# rfid1.net
KiCad netlist of a schematic drawn in EAGLE
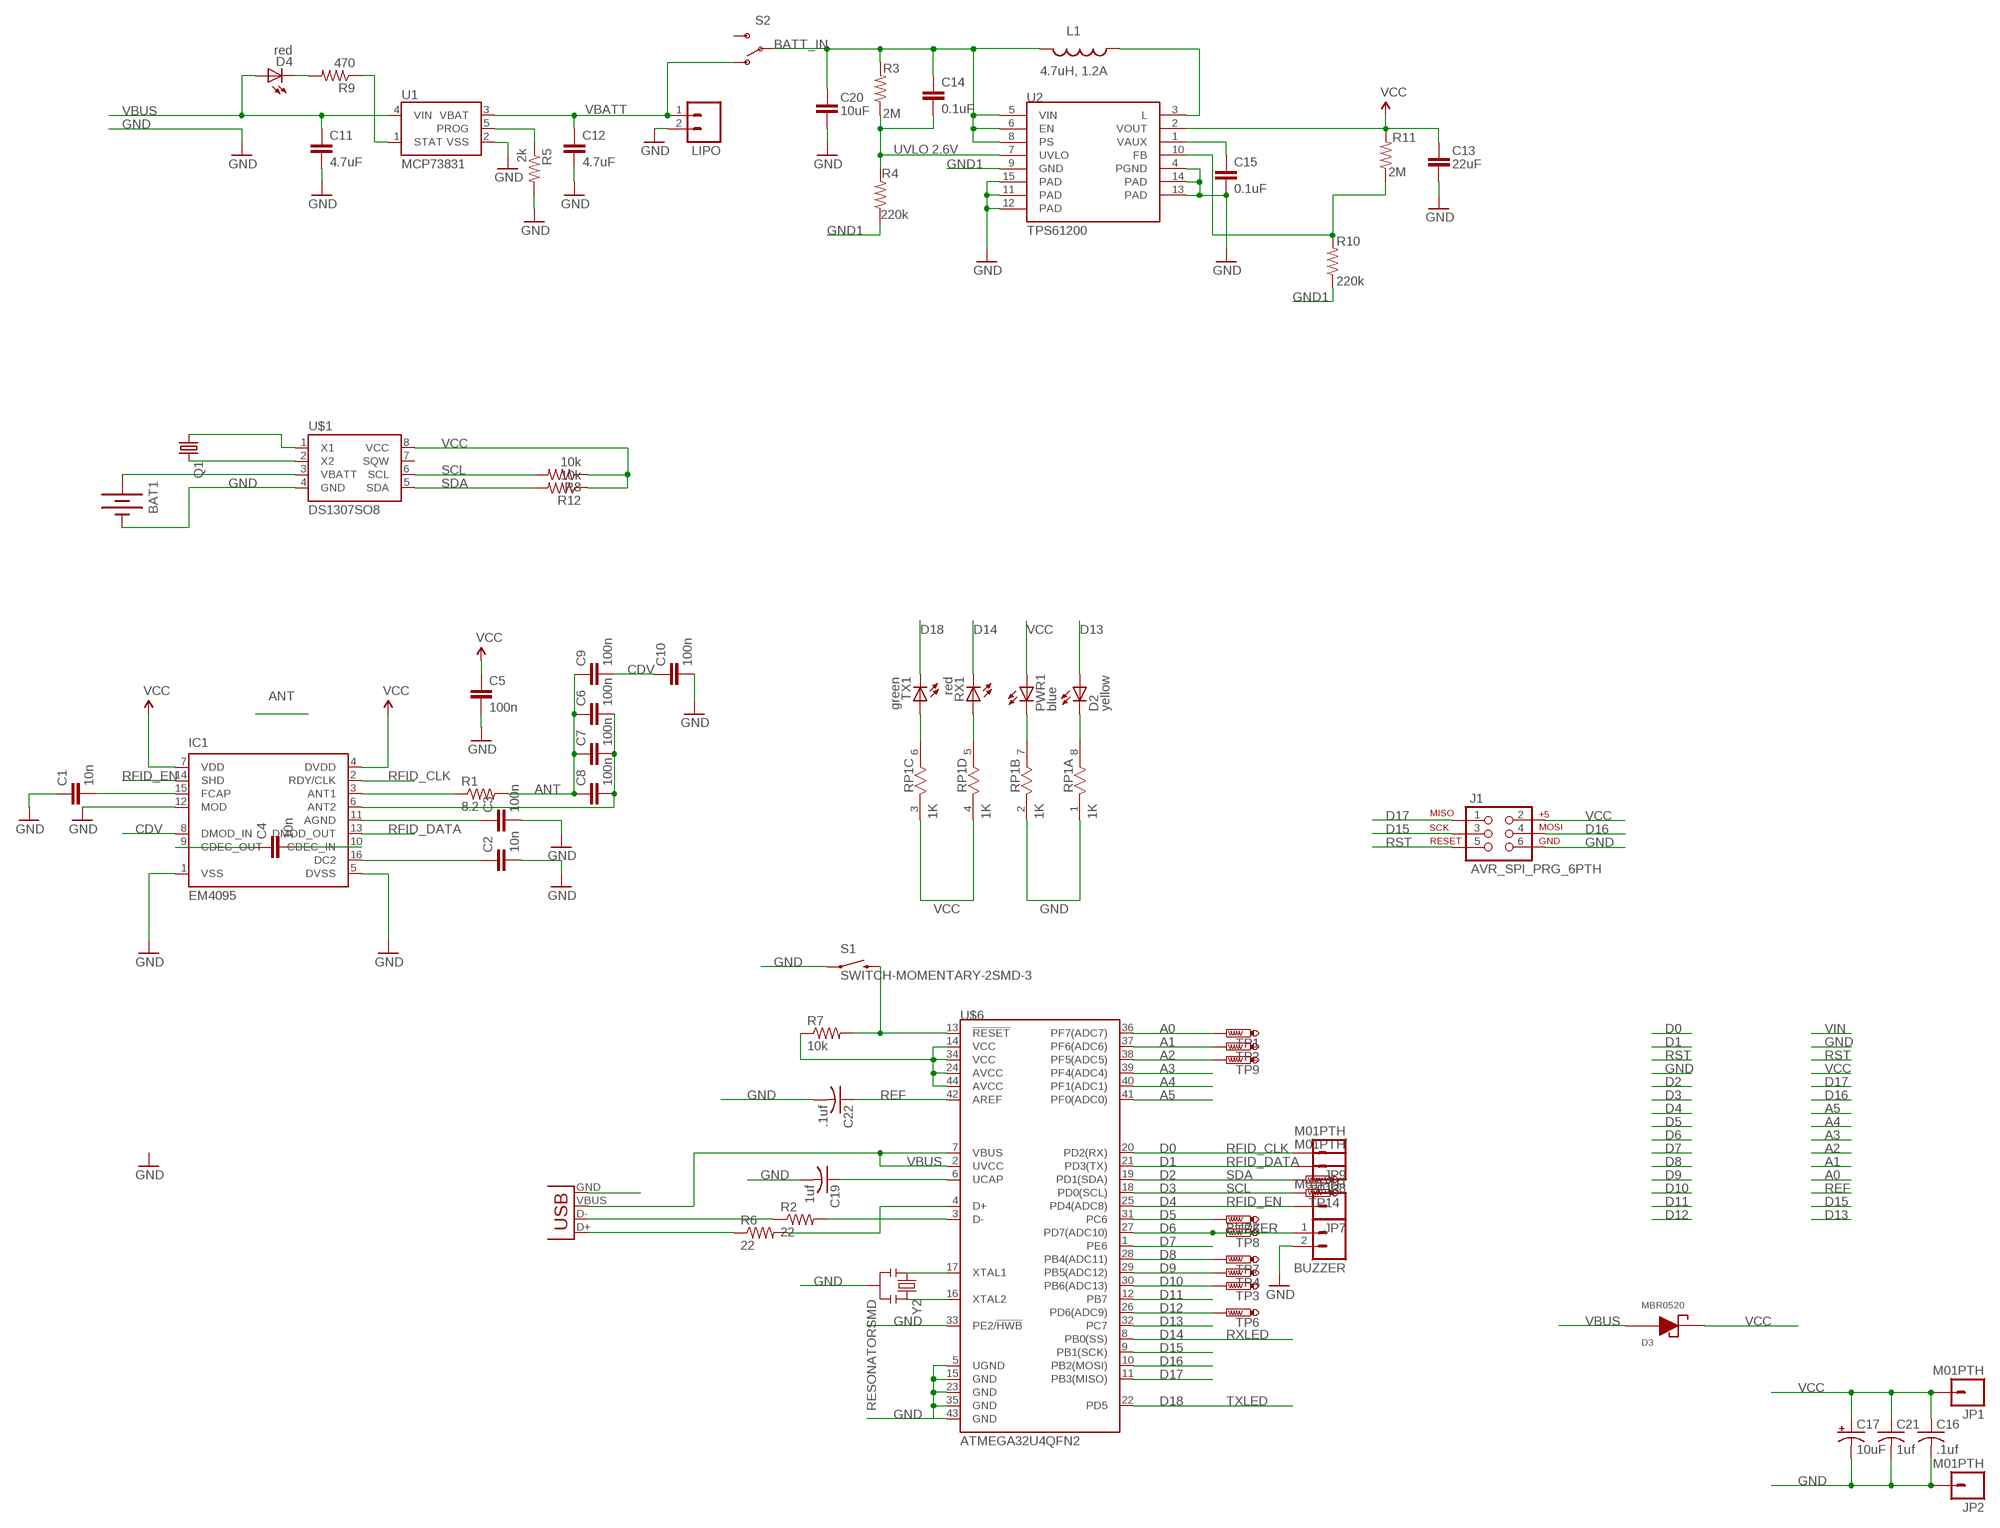
[diagram p0: schematic, sheet 1]

(export (version "E")
  (design (tool "Eeschema 10.0.6"))
  (components
    (comp (ref "BAT1")
      (value "BATTERY12MM")
      (footprint "eagle-import:BATTCON_12MM")
      (libsource (lib "eagle-import") (part "BATTERY12MM"))
    )
    (comp (ref "BUZZER")
      (value "M02PTH")
      (footprint "eagle-import:1X02")
      (libsource (lib "eagle-import") (part "M02PTH"))
    )
    (comp (ref "C1")
      (value "10n")
      (footprint "eagle-import:0805")
      (libsource (lib "eagle-import") (part "SparkFun-Passives_CAP0805"))
    )
    (comp (ref "C2")
      (value "10n")
      (footprint "eagle-import:0805")
      (libsource (lib "eagle-import") (part "SparkFun-Passives_CAP0805"))
    )
    (comp (ref "C3")
      (value "100n")
      (footprint "eagle-import:0805")
      (libsource (lib "eagle-import") (part "SparkFun-Passives_CAP0805"))
    )
    (comp (ref "C4")
      (value "10n")
      (footprint "eagle-import:0805")
      (libsource (lib "eagle-import") (part "SparkFun-Passives_CAP0805"))
    )
    (comp (ref "C5")
      (value "100n")
      (footprint "eagle-import:0805")
      (libsource (lib "eagle-import") (part "SparkFun-Passives_CAP0805"))
    )
    (comp (ref "C6")
      (value "100n")
      (footprint "eagle-import:0805")
      (libsource (lib "eagle-import") (part "SparkFun-Passives_CAP0805"))
    )
    (comp (ref "C7")
      (value "100n")
      (footprint "eagle-import:0805")
      (libsource (lib "eagle-import") (part "SparkFun-Passives_CAP0805"))
    )
    (comp (ref "C8")
      (value "100n")
      (footprint "eagle-import:0805")
      (libsource (lib "eagle-import") (part "SparkFun-Passives_CAP0805"))
    )
    (comp (ref "C9")
      (value "100n")
      (footprint "eagle-import:0805")
      (libsource (lib "eagle-import") (part "SparkFun-Passives_CAP0805"))
    )
    (comp (ref "C10")
      (value "100n")
      (footprint "eagle-import:0805")
      (libsource (lib "eagle-import") (part "SparkFun-Passives_CAP0805"))
    )
    (comp (ref "C11")
      (value "4.7uF")
      (footprint "eagle-import:0402-CAP")
      (libsource (lib "eagle-import") (part "CAP0402-CAP"))
    )
    (comp (ref "C12")
      (value "4.7uF")
      (footprint "eagle-import:0402-CAP")
      (libsource (lib "eagle-import") (part "CAP0402-CAP"))
    )
    (comp (ref "C13")
      (value "22uF")
      (footprint "eagle-import:0805")
      (libsource (lib "eagle-import") (part "CAP0805"))
    )
    (comp (ref "C14")
      (value "0.1uF")
      (footprint "eagle-import:0402-CAP")
      (libsource (lib "eagle-import") (part "CAP0402-CAP"))
    )
    (comp (ref "C15")
      (value "0.1uF")
      (footprint "eagle-import:0402-CAP")
      (libsource (lib "eagle-import") (part "CAP0402-CAP"))
    )
    (comp (ref "C16")
      (value ".1uf")
      (footprint "eagle-import:C0603")
      (libsource (lib "eagle-import") (part "C-USC0603"))
    )
    (comp (ref "C17")
      (value "10uF")
      (footprint "eagle-import:EIA3216")
      (libsource (lib "eagle-import") (part "CAP_POL1206"))
    )
    (comp (ref "C19")
      (value "1uf")
      (footprint "eagle-import:C0603")
      (libsource (lib "eagle-import") (part "C-USC0603"))
    )
    (comp (ref "C20")
      (value "10uF")
      (footprint "eagle-import:1206")
      (libsource (lib "eagle-import") (part "CAP1206"))
    )
    (comp (ref "C21")
      (value "1uf")
      (footprint "eagle-import:C0603")
      (libsource (lib "eagle-import") (part "C-USC0603"))
    )
    (comp (ref "C22")
      (value ".1uf")
      (footprint "eagle-import:C0603")
      (libsource (lib "eagle-import") (part "C-USC0603"))
    )
    (comp (ref "D2")
      (value "yellow")
      (footprint "eagle-import:CHIPLED_0805")
      (libsource (lib "eagle-import") (part "LEDCHIPLED_0805"))
    )
    (comp (ref "D3")
      (value "MBR0520")
      (footprint "eagle-import:SOD-123")
      (libsource (lib "eagle-import") (part "MBR0520"))
    )
    (comp (ref "D4")
      (value "red")
      (footprint "eagle-import:LED-0603")
      (libsource (lib "eagle-import") (part "LED0603"))
    )
    (comp (ref "IC1")
      (value "EM4095")
      (footprint "eagle-import:SO16")
      (libsource (lib "eagle-import") (part "EM4095"))
    )
    (comp (ref "J1")
      (value "AVR_SPI_PRG_6PTH")
      (footprint "eagle-import:2X3")
      (libsource (lib "eagle-import") (part "AVR_SPI_PRG_6PTH"))
    )
    (comp (ref "JP1")
      (value "M01PTH")
      (footprint "eagle-import:1X01")
      (libsource (lib "eagle-import") (part "M01PTH"))
    )
    (comp (ref "JP2")
      (value "M01PTH")
      (footprint "eagle-import:1X01")
      (libsource (lib "eagle-import") (part "M01PTH"))
    )
    (comp (ref "JP7")
      (value "M01PTH")
      (footprint "eagle-import:1X01")
      (libsource (lib "eagle-import") (part "M01PTH"))
    )
    (comp (ref "JP8")
      (value "M01PTH")
      (footprint "eagle-import:1X01")
      (libsource (lib "eagle-import") (part "M01PTH"))
    )
    (comp (ref "JP9")
      (value "M01PTH")
      (footprint "eagle-import:1X01")
      (libsource (lib "eagle-import") (part "M01PTH"))
    )
    (comp (ref "L1")
      (value "4.7uH, 1.2A")
      (footprint "eagle-import:CDRH2D09")
      (libsource (lib "eagle-import") (part "INDUCTOR."))
    )
    (comp (ref "LIPO")
      (value "M02PTH")
      (footprint "eagle-import:1X02")
      (libsource (lib "eagle-import") (part "M02PTH"))
    )
    (comp (ref "PWR1")
      (value "blue")
      (footprint "eagle-import:CHIPLED_0805")
      (libsource (lib "eagle-import") (part "LEDCHIPLED_0805"))
    )
    (comp (ref "Q1")
      (value "CRYSTALTC26H")
      (footprint "eagle-import:TC26H")
      (libsource (lib "eagle-import") (part "CRYSTALTC26H"))
    )
    (comp (ref "R1")
      (value "8.2")
      (footprint "eagle-import:0805")
      (libsource (lib "eagle-import") (part "SparkFun-Passives_RESISTOR0805-RES"))
    )
    (comp (ref "R2")
      (value "22")
      (footprint "eagle-import:0603-RES")
      (libsource (lib "eagle-import") (part "RESISTOR0603-RES"))
    )
    (comp (ref "R3")
      (value "2M")
      (footprint "eagle-import:0402-RES")
      (libsource (lib "eagle-import") (part "RESISTOR0402-RES"))
    )
    (comp (ref "R4")
      (value "220k")
      (footprint "eagle-import:0402-RES")
      (libsource (lib "eagle-import") (part "RESISTOR0402-RES"))
    )
    (comp (ref "R5")
      (value "2k")
      (footprint "eagle-import:0402-RES")
      (libsource (lib "eagle-import") (part "RESISTOR0402-RES"))
    )
    (comp (ref "R6")
      (value "22")
      (footprint "eagle-import:0603-RES")
      (libsource (lib "eagle-import") (part "RESISTOR0603-RES"))
    )
    (comp (ref "R7")
      (value "10k")
      (footprint "eagle-import:0603-RES")
      (libsource (lib "eagle-import") (part "RESISTOR0603-RES"))
    )
    (comp (ref "R8")
      (value "10k")
      (footprint "eagle-import:0603-RES")
      (libsource (lib "eagle-import") (part "RESISTOR0603-RES"))
    )
    (comp (ref "R9")
      (value "470")
      (footprint "eagle-import:0402-RES")
      (libsource (lib "eagle-import") (part "RESISTOR0402-RES"))
    )
    (comp (ref "R10")
      (value "220k")
      (footprint "eagle-import:0402-RES")
      (libsource (lib "eagle-import") (part "RESISTOR0402-RES"))
    )
    (comp (ref "R11")
      (value "2M")
      (footprint "eagle-import:0402-RES")
      (libsource (lib "eagle-import") (part "RESISTOR0402-RES"))
    )
    (comp (ref "R12")
      (value "10k")
      (footprint "eagle-import:0603-RES")
      (libsource (lib "eagle-import") (part "RESISTOR0603-RES"))
    )
    (comp (ref "RP1")
      (value "1K")
      (footprint "eagle-import:RES4NT")
      (libsource (lib "eagle-import") (part "RES4NT"))
    )
    (comp (ref "RX1")
      (value "red")
      (footprint "eagle-import:CHIPLED_0805")
      (libsource (lib "eagle-import") (part "LEDCHIPLED_0805"))
    )
    (comp (ref "S1")
      (value "SWITCH-MOMENTARY-2SMD-3")
      (footprint "eagle-import:TACTILE_SWITCH_SMD-3")
      (libsource (lib "eagle-import") (part "SWITCH-MOMENTARY-2SMD-3"))
    )
    (comp (ref "S2")
      (value "SWITCH-SPDTPTH")
      (footprint "eagle-import:SWITCH-SPDT")
      (libsource (lib "eagle-import") (part "SWITCH-SPDTPTH"))
    )
    (comp (ref "TP1")
      (value "PTR1TP15R")
      (footprint "eagle-import:TP15R")
      (libsource (lib "eagle-import") (part "PTR1TP15R"))
    )
    (comp (ref "TP2")
      (value "PTR1TP15R")
      (footprint "eagle-import:TP15R")
      (libsource (lib "eagle-import") (part "PTR1TP15R"))
    )
    (comp (ref "TP3")
      (value "PTR1TP15R")
      (footprint "eagle-import:TP15R")
      (libsource (lib "eagle-import") (part "PTR1TP15R"))
    )
    (comp (ref "TP4")
      (value "PTR1TP15R")
      (footprint "eagle-import:TP15R")
      (libsource (lib "eagle-import") (part "PTR1TP15R"))
    )
    (comp (ref "TP5")
      (value "PTR1TP15R")
      (footprint "eagle-import:TP15R")
      (libsource (lib "eagle-import") (part "PTR1TP15R"))
    )
    (comp (ref "TP6")
      (value "PTR1TP15R")
      (footprint "eagle-import:TP15R")
      (libsource (lib "eagle-import") (part "PTR1TP15R"))
    )
    (comp (ref "TP7")
      (value "PTR1TP15R")
      (footprint "eagle-import:TP15R")
      (libsource (lib "eagle-import") (part "PTR1TP15R"))
    )
    (comp (ref "TP8")
      (value "PTR1TP15R")
      (footprint "eagle-import:TP15R")
      (libsource (lib "eagle-import") (part "PTR1TP15R"))
    )
    (comp (ref "TP9")
      (value "PTR1TP15R")
      (footprint "eagle-import:TP15R")
      (libsource (lib "eagle-import") (part "PTR1TP15R"))
    )
    (comp (ref "TP13")
      (value "PTR1TP15R")
      (footprint "eagle-import:TP15R")
      (libsource (lib "eagle-import") (part "PTR1TP15R"))
    )
    (comp (ref "TP14")
      (value "PTR1TP15R")
      (footprint "eagle-import:TP15R")
      (libsource (lib "eagle-import") (part "PTR1TP15R"))
    )
    (comp (ref "TX1")
      (value "green")
      (footprint "eagle-import:CHIPLED_0805")
      (libsource (lib "eagle-import") (part "LEDCHIPLED_0805"))
    )
    (comp (ref "U$1")
      (value "DS1307SO8")
      (footprint "eagle-import:SO08")
      (libsource (lib "eagle-import") (part "DS1307SO8"))
    )
    (comp (ref "U$6")
      (value "ATMEGA32U4QFN2")
      (footprint "eagle-import:QFN-44-NOPAD")
      (libsource (lib "eagle-import") (part "ATMEGA32U4QFN2"))
    )
    (comp (ref "U1")
      (value "MCP73831")
      (footprint "eagle-import:SOT23-5")
      (libsource (lib "eagle-import") (part "MCP73831"))
    )
    (comp (ref "U2")
      (value "TPS61200")
      (footprint "eagle-import:QFN-10_PAD")
      (libsource (lib "eagle-import") (part "TPS61200"))
    )
    (comp (ref "X2")
      (value "USB-MICROB")
      (footprint "eagle-import:USB-MICROB")
      (libsource (lib "eagle-import") (part "USB-MICROB"))
    )
    (comp (ref "Y2")
      (value "RESONATORSMD")
      (footprint "eagle-import:RESONATOR-SMD")
      (libsource (lib "eagle-import") (part "RESONATORSMD"))
    )
  )
  (nets
    (net (code "1") (name "/A0") (class "Default")
      (node (ref "TP1") (pin "TP") (pinfunction "TP_TP") (pintype "input"))
      (node (ref "U$6") (pin "36") (pinfunction "PF7(ADC7)_36") (pintype "bidirectional"))
    )
    (net (code "2") (name "/A1") (class "Default")
      (node (ref "TP2") (pin "TP") (pinfunction "TP_TP") (pintype "input"))
      (node (ref "U$6") (pin "37") (pinfunction "PF6(ADC6)_37") (pintype "bidirectional"))
    )
    (net (code "3") (name "/A2") (class "Default")
      (node (ref "TP9") (pin "TP") (pinfunction "TP_TP") (pintype "input"))
      (node (ref "U$6") (pin "38") (pinfunction "PF5(ADC5)_38") (pintype "bidirectional"))
    )
    (net (code "4") (name "/A3") (class "Default")
      (node (ref "U$6") (pin "39") (pinfunction "PF4(ADC4)_39") (pintype "bidirectional"))
    )
    (net (code "5") (name "/A4") (class "Default")
      (node (ref "U$6") (pin "40") (pinfunction "PF1(ADC1)_40") (pintype "bidirectional"))
    )
    (net (code "6") (name "/A5") (class "Default")
      (node (ref "U$6") (pin "41") (pinfunction "PF0(ADC0)_41") (pintype "bidirectional"))
    )
    (net (code "7") (name "/ANT") (class "Default")
      (node (ref "C6") (pin "1") (pinfunction "1_1") (pintype "passive"))
      (node (ref "C7") (pin "1") (pinfunction "1_1") (pintype "passive"))
      (node (ref "C8") (pin "1") (pinfunction "1_1") (pintype "passive"))
      (node (ref "C9") (pin "1") (pinfunction "1_1") (pintype "passive"))
      (node (ref "R1") (pin "2") (pinfunction "2_2") (pintype "passive"))
    )
    (net (code "8") (name "/BATT_IN") (class "Default")
      (node (ref "C14") (pin "1") (pinfunction "1_1") (pintype "passive"))
      (node (ref "C20") (pin "1") (pinfunction "1_1") (pintype "passive"))
      (node (ref "L1") (pin "P$2") (pinfunction "2_P$2") (pintype "passive"))
      (node (ref "R3") (pin "2") (pinfunction "2_2") (pintype "passive"))
      (node (ref "S2") (pin "2") (pinfunction "P_2") (pintype "passive"))
      (node (ref "U2") (pin "5") (pinfunction "VIN_5") (pintype "power_in"))
      (node (ref "U2") (pin "6") (pinfunction "EN_6") (pintype "input"))
      (node (ref "U2") (pin "8") (pinfunction "PS_8") (pintype "input"))
    )
    (net (code "9") (name "/CDV") (class "Default")
      (node (ref "C10") (pin "1") (pinfunction "1_1") (pintype "passive"))
      (node (ref "C9") (pin "2") (pinfunction "2_2") (pintype "passive"))
      (node (ref "IC1") (pin "8") (pinfunction "DMOD_IN_8") (pintype "input"))
    )
    (net (code "15") (name "/D5") (class "Default")
      (node (ref "TP5") (pin "TP") (pinfunction "TP_TP") (pintype "input"))
      (node (ref "U$6") (pin "31") (pinfunction "PC6_31") (pintype "bidirectional"))
    )
    (net (code "16") (name "/D6") (class "Default")
      (node (ref "BUZZER") (pin "1") (pinfunction "1_1") (pintype "passive"))
      (node (ref "TP8") (pin "TP") (pinfunction "TP_TP") (pintype "input"))
      (node (ref "U$6") (pin "27") (pinfunction "PD7(ADC10)_27") (pintype "bidirectional"))
    )
    (net (code "17") (name "/D7") (class "Default")
      (node (ref "U$6") (pin "1") (pinfunction "PE6_1") (pintype "bidirectional"))
    )
    (net (code "18") (name "/D8") (class "Default")
      (node (ref "TP7") (pin "TP") (pinfunction "TP_TP") (pintype "input"))
      (node (ref "U$6") (pin "28") (pinfunction "PB4(ADC11)_28") (pintype "bidirectional"))
    )
    (net (code "19") (name "/D9") (class "Default")
      (node (ref "TP4") (pin "TP") (pinfunction "TP_TP") (pintype "input"))
      (node (ref "U$6") (pin "29") (pinfunction "PB5(ADC12)_29") (pintype "bidirectional"))
    )
    (net (code "20") (name "/D10") (class "Default")
      (node (ref "TP3") (pin "TP") (pinfunction "TP_TP") (pintype "input"))
      (node (ref "U$6") (pin "30") (pinfunction "PB6(ADC13)_30") (pintype "bidirectional"))
    )
    (net (code "21") (name "/D11") (class "Default")
      (node (ref "U$6") (pin "12") (pinfunction "PB7_12") (pintype "bidirectional"))
    )
    (net (code "22") (name "/D12") (class "Default")
      (node (ref "TP6") (pin "TP") (pinfunction "TP_TP") (pintype "input"))
      (node (ref "U$6") (pin "26") (pinfunction "PD6(ADC9)_26") (pintype "bidirectional"))
    )
    (net (code "23") (name "/D13") (class "Default")
      (node (ref "D2") (pin "A") (pinfunction "A_A") (pintype "passive"))
      (node (ref "U$6") (pin "32") (pinfunction "PC7_32") (pintype "bidirectional"))
    )
    (net (code "24") (name "/D14") (class "Default")
      (node (ref "RX1") (pin "C") (pinfunction "C_C") (pintype "passive"))
      (node (ref "U$6") (pin "8") (pinfunction "PB0(SS)_8") (pintype "bidirectional"))
    )
    (net (code "25") (name "/D15") (class "Default")
      (node (ref "J1") (pin "3") (pinfunction "3_3") (pintype "passive"))
      (node (ref "U$6") (pin "9") (pinfunction "PB1(SCK)_9") (pintype "bidirectional"))
    )
    (net (code "26") (name "/D16") (class "Default")
      (node (ref "J1") (pin "4") (pinfunction "4_4") (pintype "passive"))
      (node (ref "U$6") (pin "10") (pinfunction "PB2(MOSI)_10") (pintype "bidirectional"))
    )
    (net (code "27") (name "/D17") (class "Default")
      (node (ref "J1") (pin "1") (pinfunction "1_1") (pintype "passive"))
      (node (ref "U$6") (pin "11") (pinfunction "PB3(MISO)_11") (pintype "bidirectional"))
    )
    (net (code "28") (name "/D18") (class "Default")
      (node (ref "TX1") (pin "C") (pinfunction "C_C") (pintype "passive"))
      (node (ref "U$6") (pin "22") (pinfunction "PD5_22") (pintype "bidirectional"))
    )
    (net (code "29") (name "/GND1") (class "Default")
      (node (ref "R10") (pin "1") (pinfunction "1_1") (pintype "passive"))
      (node (ref "R4") (pin "1") (pinfunction "1_1") (pintype "passive"))
      (node (ref "U2") (pin "9") (pinfunction "GND_9") (pintype "power_in"))
    )
    (net (code "30") (name "/REF") (class "Default")
      (node (ref "C22") (pin "1") (pinfunction "1_1") (pintype "passive"))
      (node (ref "U$6") (pin "42") (pinfunction "AREF_42") (pintype "bidirectional"))
    )
    (net (code "31") (name "/RFID_CLK") (class "Default")
      (node (ref "IC1") (pin "2") (pinfunction "RDY/CLK_2") (pintype "output"))
      (node (ref "JP9") (pin "1") (pinfunction "1_1") (pintype "passive"))
      (node (ref "U$6") (pin "20") (pinfunction "PD2(RX)_20") (pintype "bidirectional"))
    )
    (net (code "32") (name "/RFID_DATA") (class "Default")
      (node (ref "IC1") (pin "13") (pinfunction "DMOD_OUT_13") (pintype "output"))
      (node (ref "JP8") (pin "1") (pinfunction "1_1") (pintype "passive"))
      (node (ref "U$6") (pin "21") (pinfunction "PD3(TX)_21") (pintype "bidirectional"))
    )
    (net (code "33") (name "/RFID_EN") (class "Default")
      (node (ref "IC1") (pin "14") (pinfunction "SHD_14") (pintype "input"))
      (node (ref "JP7") (pin "1") (pinfunction "1_1") (pintype "passive"))
      (node (ref "U$6") (pin "25") (pinfunction "PD4(ADC8)_25") (pintype "bidirectional"))
    )
    (net (code "34") (name "/RST") (class "Default")
      (node (ref "J1") (pin "5") (pinfunction "5_5") (pintype "passive"))
      (node (ref "R7") (pin "2") (pinfunction "2_2") (pintype "passive"))
      (node (ref "S1") (pin "P$2") (pinfunction "2_P$2") (pintype "passive"))
      (node (ref "U$6") (pin "13") (pinfunction "~{RESET}_13") (pintype "bidirectional"))
    )
    (net (code "35") (name "/SCL") (class "Default")
      (node (ref "R8") (pin "2") (pinfunction "2_2") (pintype "passive"))
      (node (ref "TP14") (pin "TP") (pinfunction "TP_TP") (pintype "input"))
      (node (ref "U$1") (pin "6") (pinfunction "SCL_6") (pintype "bidirectional"))
      (node (ref "U$6") (pin "18") (pinfunction "PD0(SCL)_18") (pintype "bidirectional"))
    )
    (net (code "36") (name "/SDA") (class "Default")
      (node (ref "R12") (pin "2") (pinfunction "2_2") (pintype "passive"))
      (node (ref "TP13") (pin "TP") (pinfunction "TP_TP") (pintype "input"))
      (node (ref "U$1") (pin "5") (pinfunction "SDA_5") (pintype "bidirectional"))
      (node (ref "U$6") (pin "19") (pinfunction "PD1(SDA)_19") (pintype "bidirectional"))
    )
    (net (code "37") (name "/VBATT") (class "Default")
      (node (ref "C12") (pin "1") (pinfunction "1_1") (pintype "passive"))
      (node (ref "LIPO") (pin "1") (pinfunction "1_1") (pintype "passive"))
      (node (ref "S2") (pin "1") (pinfunction "O_1") (pintype "passive"))
      (node (ref "U1") (pin "3") (pinfunction "VBAT_3") (pintype "power_in"))
    )
    (net (code "38") (name "/VBUS") (class "Default")
      (node (ref "C11") (pin "1") (pinfunction "1_1") (pintype "passive"))
      (node (ref "D3") (pin "2") (pinfunction "AN_2") (pintype "passive"))
      (node (ref "D4") (pin "A") (pinfunction "A_A") (pintype "passive"))
      (node (ref "U$6") (pin "2") (pinfunction "UVCC_2") (pintype "bidirectional"))
      (node (ref "U$6") (pin "7") (pinfunction "VBUS_7") (pintype "bidirectional"))
      (node (ref "U1") (pin "4") (pinfunction "VIN_4") (pintype "power_in"))
      (node (ref "X2") (pin "VBUS") (pinfunction "VBUS_VBUS") (pintype "bidirectional"))
    )
    (net (code "40") (name "GND") (class "Default")
      (node (ref "BAT1") (pin "GND") (pinfunction "-_GND") (pintype "power_in"))
      (node (ref "BUZZER") (pin "2") (pinfunction "2_2") (pintype "passive"))
      (node (ref "C1") (pin "1") (pinfunction "1_1") (pintype "passive"))
      (node (ref "C10") (pin "2") (pinfunction "2_2") (pintype "passive"))
      (node (ref "C11") (pin "2") (pinfunction "2_2") (pintype "passive"))
      (node (ref "C12") (pin "2") (pinfunction "2_2") (pintype "passive"))
      (node (ref "C13") (pin "2") (pinfunction "2_2") (pintype "passive"))
      (node (ref "C15") (pin "2") (pinfunction "2_2") (pintype "passive"))
      (node (ref "C16") (pin "2") (pinfunction "2_2") (pintype "passive"))
      (node (ref "C17") (pin "C") (pinfunction "-_C") (pintype "passive"))
      (node (ref "C19") (pin "2") (pinfunction "2_2") (pintype "passive"))
      (node (ref "C2") (pin "2") (pinfunction "2_2") (pintype "passive"))
      (node (ref "C20") (pin "2") (pinfunction "2_2") (pintype "passive"))
      (node (ref "C21") (pin "2") (pinfunction "2_2") (pintype "passive"))
      (node (ref "C22") (pin "2") (pinfunction "2_2") (pintype "passive"))
      (node (ref "C3") (pin "2") (pinfunction "2_2") (pintype "passive"))
      (node (ref "C5") (pin "2") (pinfunction "2_2") (pintype "passive"))
      (node (ref "IC1") (pin "1") (pinfunction "VSS_1") (pintype "power_in"))
      (node (ref "IC1") (pin "12") (pinfunction "MOD_12") (pintype "input"))
      (node (ref "IC1") (pin "5") (pinfunction "DVSS_5") (pintype "power_in"))
      (node (ref "J1") (pin "6") (pinfunction "6_6") (pintype "passive"))
      (node (ref "JP2") (pin "1") (pinfunction "1_1") (pintype "passive"))
      (node (ref "LIPO") (pin "2") (pinfunction "2_2") (pintype "passive"))
      (node (ref "R5") (pin "2") (pinfunction "2_2") (pintype "passive"))
      (node (ref "RP1") (pin "1") (pinfunction "1_1") (pintype "passive"))
      (node (ref "RP1") (pin "2") (pinfunction "1_2") (pintype "passive"))
      (node (ref "S1") (pin "P$1") (pinfunction "1_P$1") (pintype "passive"))
      (node (ref "U$1") (pin "4") (pinfunction "GND_4") (pintype "bidirectional"))
      (node (ref "U$6") (pin "15") (pinfunction "GND_15") (pintype "bidirectional"))
      (node (ref "U$6") (pin "23") (pinfunction "GND_23") (pintype "bidirectional"))
      (node (ref "U$6") (pin "33") (pinfunction "PE2/~{HWB}_33") (pintype "bidirectional"))
      (node (ref "U$6") (pin "35") (pinfunction "GND_35") (pintype "bidirectional"))
      (node (ref "U$6") (pin "43") (pinfunction "GND_43") (pintype "bidirectional"))
      (node (ref "U$6") (pin "5") (pinfunction "UGND_5") (pintype "bidirectional"))
      (node (ref "U1") (pin "2") (pinfunction "VSS_2") (pintype "power_in"))
      (node (ref "U2") (pin "11") (pinfunction "PAD_11") (pintype "power_in"))
      (node (ref "U2") (pin "12") (pinfunction "PAD_12") (pintype "power_in"))
      (node (ref "U2") (pin "13") (pinfunction "PAD_13") (pintype "power_in"))
      (node (ref "U2") (pin "14") (pinfunction "PAD_14") (pintype "power_in"))
      (node (ref "U2") (pin "15") (pinfunction "PAD_15") (pintype "power_in"))
      (node (ref "U2") (pin "4") (pinfunction "PGND_4") (pintype "power_in"))
      (node (ref "X2") (pin "GND") (pinfunction "GND_GND") (pintype "bidirectional"))
      (node (ref "Y2") (pin "2") (pinfunction "2_2") (pintype "passive"))
    )
    (net (code "41") (name "Net-(BAT1-+)") (class "Default")
      (node (ref "BAT1") (pin "PWR@1") (pinfunction "+_PWR@1") (pintype "power_in"))
      (node (ref "U$1") (pin "3") (pinfunction "VBATT_3") (pintype "bidirectional"))
    )
    (net (code "42") (name "Net-(D4-PadC)") (class "Default")
      (node (ref "D4") (pin "C") (pinfunction "C_C") (pintype "passive"))
      (node (ref "R9") (pin "2") (pinfunction "2_2") (pintype "passive"))
    )
    (net (code "43") (name "Net-(IC1-AGND)") (class "Default")
      (node (ref "C3") (pin "1") (pinfunction "1_1") (pintype "passive"))
      (node (ref "IC1") (pin "11") (pinfunction "AGND_11") (pintype "power_in"))
    )
    (net (code "44") (name "Net-(IC1-ANT1)") (class "Default")
      (node (ref "IC1") (pin "3") (pinfunction "ANT1_3") (pintype "passive"))
      (node (ref "R1") (pin "1") (pinfunction "1_1") (pintype "passive"))
    )
    (net (code "45") (name "Net-(IC1-ANT2)") (class "Default")
      (node (ref "C6") (pin "2") (pinfunction "2_2") (pintype "passive"))
      (node (ref "C7") (pin "2") (pinfunction "2_2") (pintype "passive"))
      (node (ref "C8") (pin "2") (pinfunction "2_2") (pintype "passive"))
      (node (ref "IC1") (pin "6") (pinfunction "ANT2_6") (pintype "passive"))
    )
    (net (code "46") (name "Net-(IC1-CDEC_IN)") (class "Default")
      (node (ref "C4") (pin "2") (pinfunction "2_2") (pintype "passive"))
      (node (ref "IC1") (pin "10") (pinfunction "CDEC_IN_10") (pintype "input"))
    )
    (net (code "47") (name "Net-(IC1-CDEC_OUT)") (class "Default")
      (node (ref "C4") (pin "1") (pinfunction "1_1") (pintype "passive"))
      (node (ref "IC1") (pin "9") (pinfunction "CDEC_OUT_9") (pintype "output"))
    )
    (net (code "48") (name "Net-(IC1-DC2)") (class "Default")
      (node (ref "C2") (pin "1") (pinfunction "1_1") (pintype "passive"))
      (node (ref "IC1") (pin "16") (pinfunction "DC2_16") (pintype "passive"))
    )
    (net (code "49") (name "Net-(IC1-FCAP)") (class "Default")
      (node (ref "C1") (pin "2") (pinfunction "2_2") (pintype "passive"))
      (node (ref "IC1") (pin "15") (pinfunction "FCAP_15") (pintype "passive"))
    )
    (net (code "50") (name "Net-(L1-1)") (class "Default")
      (node (ref "L1") (pin "P$1") (pinfunction "1_P$1") (pintype "passive"))
      (node (ref "U2") (pin "3") (pinfunction "L_3") (pintype "passive"))
    )
    (net (code "51") (name "Net-(R2-Pad1)") (class "Default")
      (node (ref "R2") (pin "1") (pinfunction "1_1") (pintype "passive"))
      (node (ref "X2") (pin "D-") (pinfunction "D-_D-") (pintype "bidirectional"))
    )
    (net (code "52") (name "Net-(R6-Pad1)") (class "Default")
      (node (ref "R6") (pin "1") (pinfunction "1_1") (pintype "passive"))
      (node (ref "X2") (pin "D+") (pinfunction "D+_D+") (pintype "bidirectional"))
    )
    (net (code "53") (name "Net-(RP1A-2)") (class "Default")
      (node (ref "D2") (pin "C") (pinfunction "C_C") (pintype "passive"))
      (node (ref "RP1") (pin "8") (pinfunction "2_8") (pintype "passive"))
    )
    (net (code "54") (name "Net-(RP1B-2)") (class "Default")
      (node (ref "PWR1") (pin "C") (pinfunction "C_C") (pintype "passive"))
      (node (ref "RP1") (pin "7") (pinfunction "2_7") (pintype "passive"))
    )
    (net (code "55") (name "Net-(RP1C-2)") (class "Default")
      (node (ref "RP1") (pin "6") (pinfunction "2_6") (pintype "passive"))
      (node (ref "TX1") (pin "A") (pinfunction "A_A") (pintype "passive"))
    )
    (net (code "56") (name "Net-(RP1D-2)") (class "Default")
      (node (ref "RP1") (pin "5") (pinfunction "2_5") (pintype "passive"))
      (node (ref "RX1") (pin "A") (pinfunction "A_A") (pintype "passive"))
    )
    (net (code "57") (name "Net-(U$1-X1)") (class "Default")
      (node (ref "Q1") (pin "1") (pinfunction "1_1") (pintype "passive"))
      (node (ref "U$1") (pin "1") (pinfunction "X1_1") (pintype "bidirectional"))
    )
    (net (code "58") (name "Net-(U$1-X2)") (class "Default")
      (node (ref "Q1") (pin "2") (pinfunction "2_2") (pintype "passive"))
      (node (ref "U$1") (pin "2") (pinfunction "X2_2") (pintype "bidirectional"))
    )
    (net (code "59") (name "Net-(U$6-D+)") (class "Default")
      (node (ref "R6") (pin "2") (pinfunction "2_2") (pintype "passive"))
      (node (ref "U$6") (pin "4") (pinfunction "D+_4") (pintype "bidirectional"))
    )
    (net (code "60") (name "Net-(U$6-D-)") (class "Default")
      (node (ref "R2") (pin "2") (pinfunction "2_2") (pintype "passive"))
      (node (ref "U$6") (pin "3") (pinfunction "D-_3") (pintype "bidirectional"))
    )
    (net (code "61") (name "Net-(U$6-UCAP)") (class "Default")
      (node (ref "C19") (pin "1") (pinfunction "1_1") (pintype "passive"))
      (node (ref "U$6") (pin "6") (pinfunction "UCAP_6") (pintype "bidirectional"))
    )
    (net (code "62") (name "Net-(U$6-XTAL1)") (class "Default")
      (node (ref "U$6") (pin "17") (pinfunction "XTAL1_17") (pintype "bidirectional"))
      (node (ref "Y2") (pin "1") (pinfunction "1_1") (pintype "passive"))
    )
    (net (code "63") (name "Net-(U$6-XTAL2)") (class "Default")
      (node (ref "U$6") (pin "16") (pinfunction "XTAL2_16") (pintype "bidirectional"))
      (node (ref "Y2") (pin "3") (pinfunction "3_3") (pintype "passive"))
    )
    (net (code "64") (name "Net-(U1-PROG)") (class "Default")
      (node (ref "R5") (pin "1") (pinfunction "1_1") (pintype "passive"))
      (node (ref "U1") (pin "5") (pinfunction "PROG_5") (pintype "input"))
    )
    (net (code "65") (name "Net-(U1-STAT)") (class "Default")
      (node (ref "R9") (pin "1") (pinfunction "1_1") (pintype "passive"))
      (node (ref "U1") (pin "1") (pinfunction "STAT_1") (pintype "output"))
    )
    (net (code "66") (name "Net-(U2-FB)") (class "Default")
      (node (ref "R10") (pin "2") (pinfunction "2_2") (pintype "passive"))
      (node (ref "R11") (pin "1") (pinfunction "1_1") (pintype "passive"))
      (node (ref "U2") (pin "10") (pinfunction "FB_10") (pintype "passive"))
    )
    (net (code "67") (name "Net-(U2-UVLO)") (class "Default")
      (node (ref "C14") (pin "2") (pinfunction "2_2") (pintype "passive"))
      (node (ref "R3") (pin "1") (pinfunction "1_1") (pintype "passive"))
      (node (ref "R4") (pin "2") (pinfunction "2_2") (pintype "passive"))
      (node (ref "U2") (pin "7") (pinfunction "UVLO_7") (pintype "passive"))
    )
    (net (code "68") (name "Net-(U2-VAUX)") (class "Default")
      (node (ref "C15") (pin "1") (pinfunction "1_1") (pintype "passive"))
      (node (ref "U2") (pin "1") (pinfunction "VAUX_1") (pintype "passive"))
    )
    (net (code "69") (name "VCC") (class "Default")
      (node (ref "C13") (pin "1") (pinfunction "1_1") (pintype "passive"))
      (node (ref "C16") (pin "1") (pinfunction "1_1") (pintype "passive"))
      (node (ref "C17") (pin "A") (pinfunction "+_A") (pintype "passive"))
      (node (ref "C21") (pin "1") (pinfunction "1_1") (pintype "passive"))
      (node (ref "C5") (pin "1") (pinfunction "1_1") (pintype "passive"))
      (node (ref "D3") (pin "1") (pinfunction "CA_1") (pintype "passive"))
      (node (ref "IC1") (pin "4") (pinfunction "DVDD_4") (pintype "power_in"))
      (node (ref "IC1") (pin "7") (pinfunction "VDD_7") (pintype "power_in"))
      (node (ref "J1") (pin "2") (pinfunction "2_2") (pintype "passive"))
      (node (ref "JP1") (pin "1") (pinfunction "1_1") (pintype "passive"))
      (node (ref "PWR1") (pin "A") (pinfunction "A_A") (pintype "passive"))
      (node (ref "R11") (pin "2") (pinfunction "2_2") (pintype "passive"))
      (node (ref "R12") (pin "1") (pinfunction "1_1") (pintype "passive"))
      (node (ref "R7") (pin "1") (pinfunction "1_1") (pintype "passive"))
      (node (ref "R8") (pin "1") (pinfunction "1_1") (pintype "passive"))
      (node (ref "RP1") (pin "3") (pinfunction "1_3") (pintype "passive"))
      (node (ref "RP1") (pin "4") (pinfunction "1_4") (pintype "passive"))
      (node (ref "U$1") (pin "8") (pinfunction "VCC_8") (pintype "bidirectional"))
      (node (ref "U$6") (pin "14") (pinfunction "VCC_14") (pintype "bidirectional"))
      (node (ref "U$6") (pin "24") (pinfunction "AVCC_24") (pintype "bidirectional"))
      (node (ref "U$6") (pin "34") (pinfunction "VCC_34") (pintype "bidirectional"))
      (node (ref "U$6") (pin "44") (pinfunction "AVCC_44") (pintype "bidirectional"))
      (node (ref "U2") (pin "2") (pinfunction "VOUT_2") (pintype "passive"))
    )
    (net (code "70") (name "unconnected-(S2-S-Pad3)") (class "Default")
      (node (ref "S2") (pin "3") (pinfunction "S_3") (pintype "passive"))
    )
    (net (code "71") (name "unconnected-(U$1-SQW-Pad7)") (class "Default")
      (node (ref "U$1") (pin "7") (pinfunction "SQW_7") (pintype "bidirectional"))
    )
  )
)
